# working.net
KiCad netlist of a schematic drawn in EAGLE
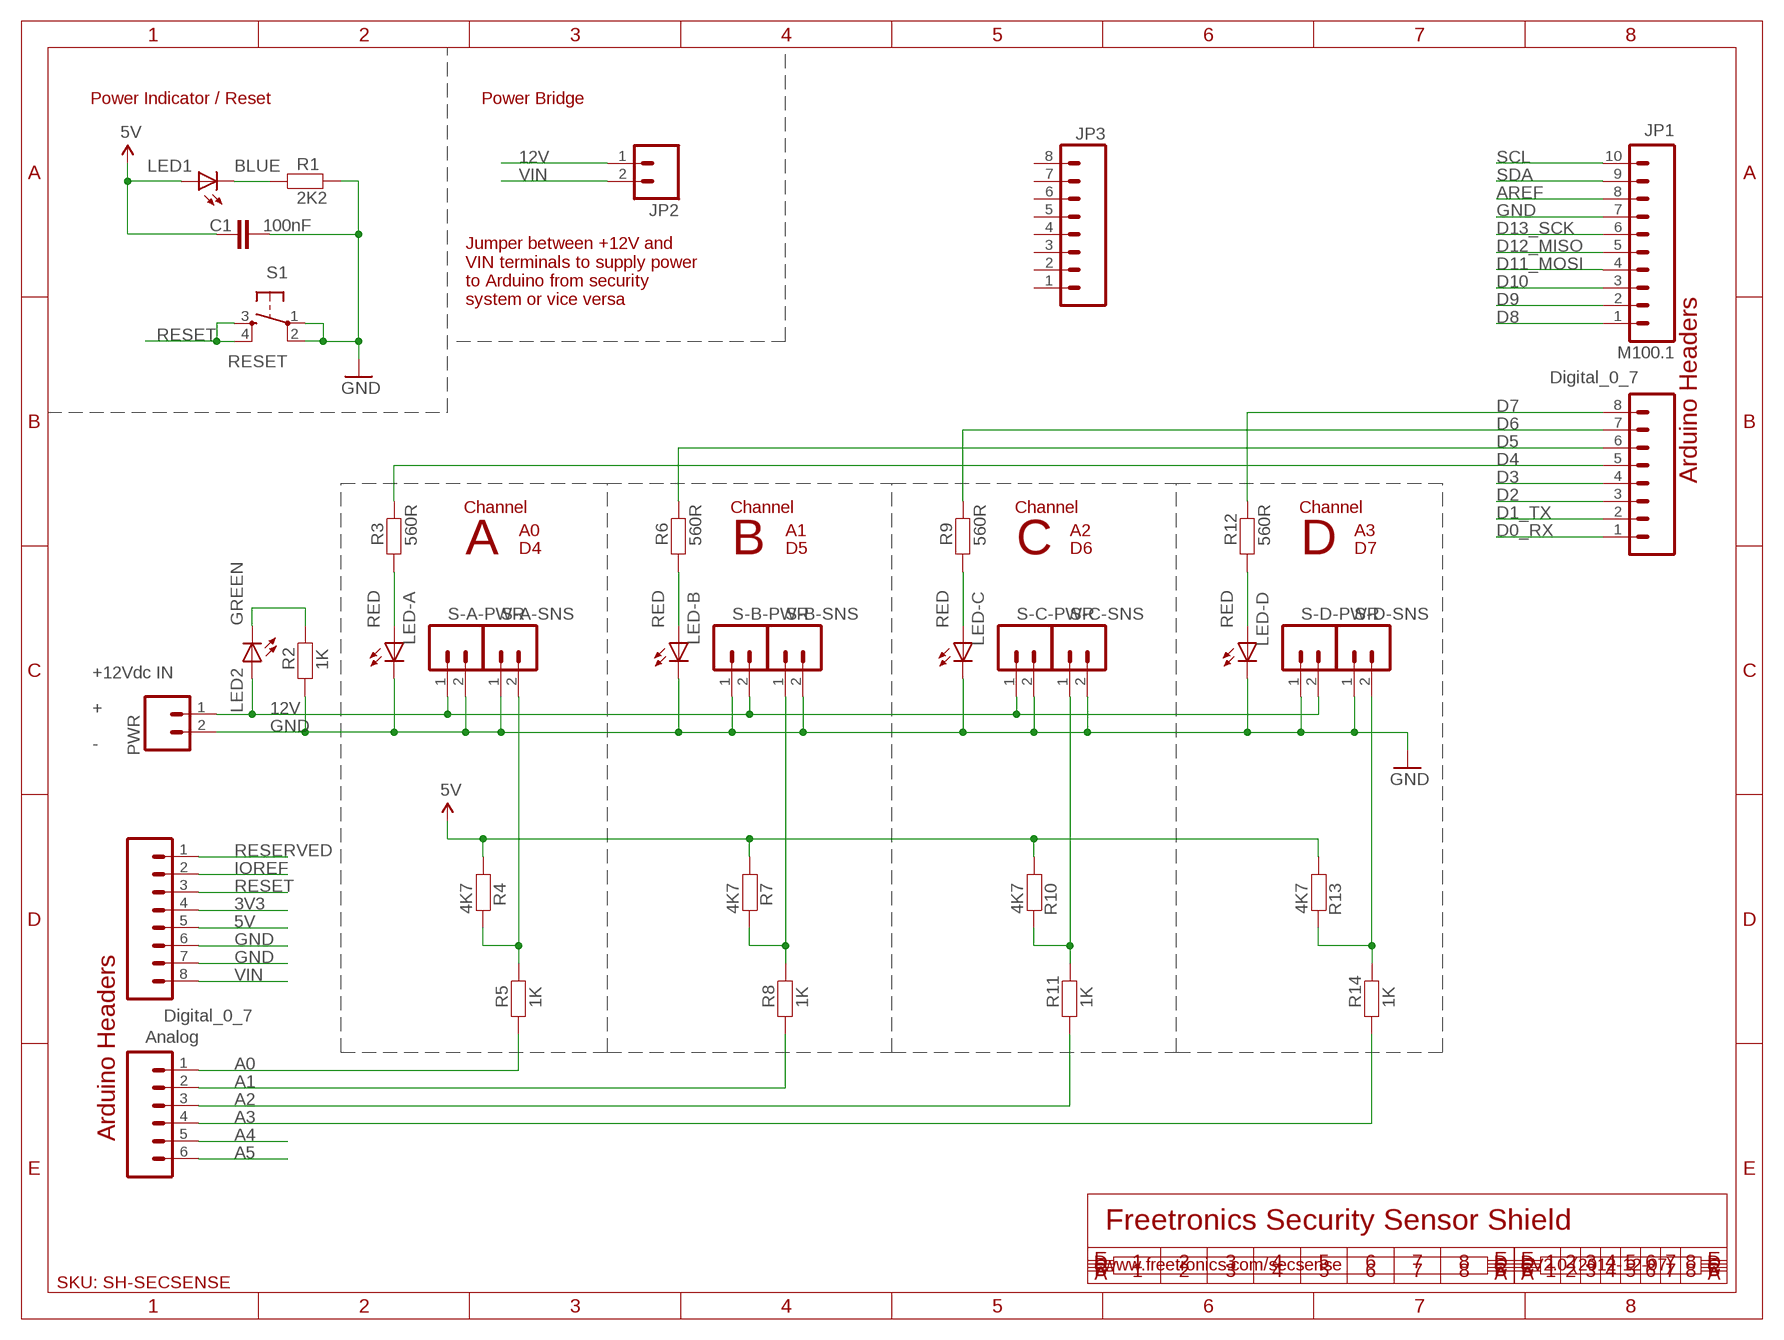
[diagram p0: schematic, sheet 1]

(export (version "E")
  (design (tool "Eeschema 10.0.6"))
  (components
    (comp (ref "C1")
      (value "100nF")
      (footprint "eagle-import:FREETRONICS_CAP-PTH-SMALL")
      (libsource (lib "eagle-import") (part "FREETRONICS_CAPPTH"))
    )
    (comp (ref "J1")
      (value "Digital_0_7")
      (footprint "eagle-import:1X08")
      (libsource (lib "eagle-import") (part "M08"))
    )
    (comp (ref "J2")
      (value "Analog")
      (footprint "eagle-import:1X06")
      (libsource (lib "eagle-import") (part "M06SIP"))
    )
    (comp (ref "J3")
      (value "Digital_0_7")
      (footprint "eagle-import:1X08")
      (libsource (lib "eagle-import") (part "M08"))
    )
    (comp (ref "JP1")
      (value "M100.1")
      (footprint "eagle-import:1X10")
      (libsource (lib "eagle-import") (part "M100.1"))
    )
    (comp (ref "JP2")
      (value "M02PTH")
      (footprint "eagle-import:1X02")
      (libsource (lib "eagle-import") (part "freetronics-original_M02PTH"))
    )
    (comp (ref "JP3")
      (value "M08")
      (footprint "eagle-import:TERMINALBLOCK_3.5MM_8")
      (libsource (lib "eagle-import") (part "freetronics-master-v1_M08"))
    )
    (comp (ref "LED-A")
      (value "RED")
      (footprint "eagle-import:LED3MM")
      (libsource (lib "eagle-import") (part "LED3MM"))
    )
    (comp (ref "LED-B")
      (value "RED")
      (footprint "eagle-import:LED3MM")
      (libsource (lib "eagle-import") (part "LED3MM"))
    )
    (comp (ref "LED-C")
      (value "RED")
      (footprint "eagle-import:LED3MM")
      (libsource (lib "eagle-import") (part "LED3MM"))
    )
    (comp (ref "LED-D")
      (value "RED")
      (footprint "eagle-import:LED3MM")
      (libsource (lib "eagle-import") (part "LED3MM"))
    )
    (comp (ref "LED1")
      (value "BLUE")
      (footprint "eagle-import:LED3MM")
      (libsource (lib "eagle-import") (part "LED3MM"))
    )
    (comp (ref "LED2")
      (value "GREEN")
      (footprint "eagle-import:LED3MM")
      (libsource (lib "eagle-import") (part "LED3MM"))
    )
    (comp (ref "PWR")
      (value "M025MM")
      (footprint "eagle-import:SCREWTERMINAL-5MM-2")
      (libsource (lib "eagle-import") (part "M025MM"))
    )
    (comp (ref "R1")
      (value "2K2")
      (footprint "eagle-import:FREETRONICS_AXIAL-0.4")
      (libsource (lib "eagle-import") (part "FREETRONICS_RESISTORPTH2"))
    )
    (comp (ref "R2")
      (value "1K")
      (footprint "eagle-import:FREETRONICS_AXIAL-0.4")
      (libsource (lib "eagle-import") (part "FREETRONICS_RESISTORPTH2"))
    )
    (comp (ref "R3")
      (value "560R")
      (footprint "eagle-import:FREETRONICS_AXIAL-0.4")
      (libsource (lib "eagle-import") (part "FREETRONICS_RESISTORPTH2"))
    )
    (comp (ref "R4")
      (value "4K7")
      (footprint "eagle-import:FREETRONICS_AXIAL-0.4")
      (libsource (lib "eagle-import") (part "FREETRONICS_RESISTORPTH2"))
    )
    (comp (ref "R5")
      (value "1K")
      (footprint "eagle-import:FREETRONICS_AXIAL-0.4")
      (libsource (lib "eagle-import") (part "FREETRONICS_RESISTORPTH2"))
    )
    (comp (ref "R6")
      (value "560R")
      (footprint "eagle-import:FREETRONICS_AXIAL-0.4")
      (libsource (lib "eagle-import") (part "FREETRONICS_RESISTORPTH2"))
    )
    (comp (ref "R7")
      (value "4K7")
      (footprint "eagle-import:FREETRONICS_AXIAL-0.4")
      (libsource (lib "eagle-import") (part "FREETRONICS_RESISTORPTH2"))
    )
    (comp (ref "R8")
      (value "1K")
      (footprint "eagle-import:FREETRONICS_AXIAL-0.4")
      (libsource (lib "eagle-import") (part "FREETRONICS_RESISTORPTH2"))
    )
    (comp (ref "R9")
      (value "560R")
      (footprint "eagle-import:FREETRONICS_AXIAL-0.4")
      (libsource (lib "eagle-import") (part "FREETRONICS_RESISTORPTH2"))
    )
    (comp (ref "R10")
      (value "4K7")
      (footprint "eagle-import:FREETRONICS_AXIAL-0.4")
      (libsource (lib "eagle-import") (part "FREETRONICS_RESISTORPTH2"))
    )
    (comp (ref "R11")
      (value "1K")
      (footprint "eagle-import:FREETRONICS_AXIAL-0.4")
      (libsource (lib "eagle-import") (part "FREETRONICS_RESISTORPTH2"))
    )
    (comp (ref "R12")
      (value "560R")
      (footprint "eagle-import:FREETRONICS_AXIAL-0.4")
      (libsource (lib "eagle-import") (part "FREETRONICS_RESISTORPTH2"))
    )
    (comp (ref "R13")
      (value "4K7")
      (footprint "eagle-import:FREETRONICS_AXIAL-0.4")
      (libsource (lib "eagle-import") (part "FREETRONICS_RESISTORPTH2"))
    )
    (comp (ref "R14")
      (value "1K")
      (footprint "eagle-import:FREETRONICS_AXIAL-0.4")
      (libsource (lib "eagle-import") (part "FREETRONICS_RESISTORPTH2"))
    )
    (comp (ref "S-A-PWR")
      (value "M025MM")
      (footprint "eagle-import:SCREWTERMINAL-5MM-2")
      (libsource (lib "eagle-import") (part "M025MM"))
    )
    (comp (ref "S-A-SNS")
      (value "M025MM")
      (footprint "eagle-import:SCREWTERMINAL-5MM-2")
      (libsource (lib "eagle-import") (part "M025MM"))
    )
    (comp (ref "S-B-PWR")
      (value "M025MM")
      (footprint "eagle-import:SCREWTERMINAL-5MM-2")
      (libsource (lib "eagle-import") (part "M025MM"))
    )
    (comp (ref "S-B-SNS")
      (value "M025MM")
      (footprint "eagle-import:SCREWTERMINAL-5MM-2")
      (libsource (lib "eagle-import") (part "M025MM"))
    )
    (comp (ref "S-C-PWR")
      (value "M025MM")
      (footprint "eagle-import:SCREWTERMINAL-5MM-2")
      (libsource (lib "eagle-import") (part "M025MM"))
    )
    (comp (ref "S-C-SNS")
      (value "M025MM")
      (footprint "eagle-import:SCREWTERMINAL-5MM-2")
      (libsource (lib "eagle-import") (part "M025MM"))
    )
    (comp (ref "S-D-PWR")
      (value "M025MM")
      (footprint "eagle-import:SCREWTERMINAL-5MM-2")
      (libsource (lib "eagle-import") (part "M025MM"))
    )
    (comp (ref "S-D-SNS")
      (value "M025MM")
      (footprint "eagle-import:SCREWTERMINAL-5MM-2")
      (libsource (lib "eagle-import") (part "M025MM"))
    )
    (comp (ref "S1")
      (value "RESET")
      (footprint "eagle-import:FREETRONICS_TACTILE-PTH")
      (libsource (lib "eagle-import") (part "FREETRONICS_TAC_SWITCHPTH"))
    )
  )
  (nets
    (net (code "1") (name "/3V3") (class "Default")
      (node (ref "J3") (pin "4") (pinfunction "4_4") (pintype "passive"))
    )
    (net (code "2") (name "/12V") (class "Default")
      (node (ref "JP2") (pin "1") (pinfunction "1_1") (pintype "passive"))
      (node (ref "LED2") (pin "A") (pinfunction "A_A") (pintype "passive"))
      (node (ref "PWR") (pin "1") (pinfunction "1_1") (pintype "passive"))
      (node (ref "S-A-PWR") (pin "1") (pinfunction "1_1") (pintype "passive"))
      (node (ref "S-B-PWR") (pin "2") (pinfunction "2_2") (pintype "passive"))
      (node (ref "S-C-PWR") (pin "1") (pinfunction "1_1") (pintype "passive"))
      (node (ref "S-D-PWR") (pin "2") (pinfunction "2_2") (pintype "passive"))
    )
    (net (code "3") (name "/A0") (class "Default")
      (node (ref "J2") (pin "1") (pinfunction "1_1") (pintype "passive"))
      (node (ref "R5") (pin "P$1") (pinfunction "1_P$1") (pintype "passive"))
    )
    (net (code "4") (name "/A1") (class "Default")
      (node (ref "J2") (pin "2") (pinfunction "2_2") (pintype "passive"))
      (node (ref "R8") (pin "P$1") (pinfunction "1_P$1") (pintype "passive"))
    )
    (net (code "5") (name "/A2") (class "Default")
      (node (ref "J2") (pin "3") (pinfunction "3_3") (pintype "passive"))
      (node (ref "R11") (pin "P$1") (pinfunction "1_P$1") (pintype "passive"))
    )
    (net (code "6") (name "/A3") (class "Default")
      (node (ref "J2") (pin "4") (pinfunction "4_4") (pintype "passive"))
      (node (ref "R14") (pin "P$1") (pinfunction "1_P$1") (pintype "passive"))
    )
    (net (code "7") (name "/A4") (class "Default")
      (node (ref "J2") (pin "5") (pinfunction "5_5") (pintype "passive"))
    )
    (net (code "8") (name "/A5") (class "Default")
      (node (ref "J2") (pin "6") (pinfunction "6_6") (pintype "passive"))
    )
    (net (code "9") (name "/AREF") (class "Default")
      (node (ref "JP1") (pin "8") (pinfunction "8_8") (pintype "passive"))
    )
    (net (code "10") (name "/D0_RX") (class "Default")
      (node (ref "J1") (pin "1") (pinfunction "1_1") (pintype "passive"))
    )
    (net (code "11") (name "/D1_TX") (class "Default")
      (node (ref "J1") (pin "2") (pinfunction "2_2") (pintype "passive"))
    )
    (net (code "12") (name "/D2") (class "Default")
      (node (ref "J1") (pin "3") (pinfunction "3_3") (pintype "passive"))
    )
    (net (code "13") (name "/D3") (class "Default")
      (node (ref "J1") (pin "4") (pinfunction "4_4") (pintype "passive"))
    )
    (net (code "14") (name "/D4") (class "Default")
      (node (ref "J1") (pin "5") (pinfunction "5_5") (pintype "passive"))
      (node (ref "R3") (pin "P$2") (pinfunction "2_P$2") (pintype "passive"))
    )
    (net (code "15") (name "/D5") (class "Default")
      (node (ref "J1") (pin "6") (pinfunction "6_6") (pintype "passive"))
      (node (ref "R6") (pin "P$2") (pinfunction "2_P$2") (pintype "passive"))
    )
    (net (code "16") (name "/D6") (class "Default")
      (node (ref "J1") (pin "7") (pinfunction "7_7") (pintype "passive"))
      (node (ref "R9") (pin "P$2") (pinfunction "2_P$2") (pintype "passive"))
    )
    (net (code "17") (name "/D7") (class "Default")
      (node (ref "J1") (pin "8") (pinfunction "8_8") (pintype "passive"))
      (node (ref "R12") (pin "P$2") (pinfunction "2_P$2") (pintype "passive"))
    )
    (net (code "18") (name "/D8") (class "Default")
      (node (ref "JP1") (pin "1") (pinfunction "1_1") (pintype "passive"))
    )
    (net (code "19") (name "/D9") (class "Default")
      (node (ref "JP1") (pin "2") (pinfunction "2_2") (pintype "passive"))
    )
    (net (code "20") (name "/D10") (class "Default")
      (node (ref "JP1") (pin "3") (pinfunction "3_3") (pintype "passive"))
    )
    (net (code "21") (name "/D11_MOSI") (class "Default")
      (node (ref "JP1") (pin "4") (pinfunction "4_4") (pintype "passive"))
    )
    (net (code "22") (name "/D12_MISO") (class "Default")
      (node (ref "JP1") (pin "5") (pinfunction "5_5") (pintype "passive"))
    )
    (net (code "23") (name "/D13_SCK") (class "Default")
      (node (ref "JP1") (pin "6") (pinfunction "6_6") (pintype "passive"))
    )
    (net (code "24") (name "/IOREF") (class "Default")
      (node (ref "J3") (pin "2") (pinfunction "2_2") (pintype "passive"))
    )
    (net (code "25") (name "/RESERVED") (class "Default")
      (node (ref "J3") (pin "1") (pinfunction "1_1") (pintype "passive"))
    )
    (net (code "26") (name "/RESET") (class "Default")
      (node (ref "J3") (pin "3") (pinfunction "3_3") (pintype "passive"))
      (node (ref "S1") (pin "3") (pinfunction "3_3") (pintype "passive"))
      (node (ref "S1") (pin "4") (pinfunction "4_4") (pintype "passive"))
    )
    (net (code "27") (name "/SCL") (class "Default")
      (node (ref "JP1") (pin "10") (pinfunction "10_10") (pintype "passive"))
    )
    (net (code "28") (name "/SDA") (class "Default")
      (node (ref "JP1") (pin "9") (pinfunction "9_9") (pintype "passive"))
    )
    (net (code "29") (name "/VIN") (class "Default")
      (node (ref "J3") (pin "8") (pinfunction "8_8") (pintype "passive"))
      (node (ref "JP2") (pin "2") (pinfunction "2_2") (pintype "passive"))
    )
    (net (code "30") (name "5V") (class "Default")
      (node (ref "C1") (pin "1") (pinfunction "1_1") (pintype "passive"))
      (node (ref "J3") (pin "5") (pinfunction "5_5") (pintype "passive"))
      (node (ref "LED1") (pin "A") (pinfunction "A_A") (pintype "passive"))
      (node (ref "R10") (pin "P$1") (pinfunction "1_P$1") (pintype "passive"))
      (node (ref "R13") (pin "P$1") (pinfunction "1_P$1") (pintype "passive"))
      (node (ref "R4") (pin "P$1") (pinfunction "1_P$1") (pintype "passive"))
      (node (ref "R7") (pin "P$1") (pinfunction "1_P$1") (pintype "passive"))
    )
    (net (code "31") (name "GND") (class "Default")
      (node (ref "C1") (pin "2") (pinfunction "2_2") (pintype "passive"))
      (node (ref "J3") (pin "6") (pinfunction "6_6") (pintype "passive"))
      (node (ref "J3") (pin "7") (pinfunction "7_7") (pintype "passive"))
      (node (ref "JP1") (pin "7") (pinfunction "7_7") (pintype "passive"))
      (node (ref "LED-A") (pin "K") (pinfunction "C_K") (pintype "passive"))
      (node (ref "LED-B") (pin "K") (pinfunction "C_K") (pintype "passive"))
      (node (ref "LED-C") (pin "K") (pinfunction "C_K") (pintype "passive"))
      (node (ref "LED-D") (pin "K") (pinfunction "C_K") (pintype "passive"))
      (node (ref "PWR") (pin "2") (pinfunction "2_2") (pintype "passive"))
      (node (ref "R1") (pin "P$2") (pinfunction "2_P$2") (pintype "passive"))
      (node (ref "R2") (pin "P$1") (pinfunction "1_P$1") (pintype "passive"))
      (node (ref "S-A-PWR") (pin "2") (pinfunction "2_2") (pintype "passive"))
      (node (ref "S-A-SNS") (pin "1") (pinfunction "1_1") (pintype "passive"))
      (node (ref "S-B-PWR") (pin "1") (pinfunction "1_1") (pintype "passive"))
      (node (ref "S-B-SNS") (pin "2") (pinfunction "2_2") (pintype "passive"))
      (node (ref "S-C-PWR") (pin "2") (pinfunction "2_2") (pintype "passive"))
      (node (ref "S-C-SNS") (pin "2") (pinfunction "2_2") (pintype "passive"))
      (node (ref "S-D-PWR") (pin "1") (pinfunction "1_1") (pintype "passive"))
      (node (ref "S-D-SNS") (pin "1") (pinfunction "1_1") (pintype "passive"))
      (node (ref "S1") (pin "1") (pinfunction "1_1") (pintype "passive"))
      (node (ref "S1") (pin "2") (pinfunction "2_2") (pintype "passive"))
    )
    (net (code "32") (name "Net-(LED1-C)") (class "Default")
      (node (ref "LED1") (pin "K") (pinfunction "C_K") (pintype "passive"))
      (node (ref "R1") (pin "P$1") (pinfunction "1_P$1") (pintype "passive"))
    )
    (net (code "33") (name "Net-(LED2-C)") (class "Default")
      (node (ref "LED2") (pin "K") (pinfunction "C_K") (pintype "passive"))
      (node (ref "R2") (pin "P$2") (pinfunction "2_P$2") (pintype "passive"))
    )
    (net (code "34") (name "Net-(R3-1)") (class "Default")
      (node (ref "LED-A") (pin "A") (pinfunction "A_A") (pintype "passive"))
      (node (ref "R3") (pin "P$1") (pinfunction "1_P$1") (pintype "passive"))
    )
    (net (code "35") (name "Net-(R4-2)") (class "Default")
      (node (ref "R4") (pin "P$2") (pinfunction "2_P$2") (pintype "passive"))
      (node (ref "R5") (pin "P$2") (pinfunction "2_P$2") (pintype "passive"))
      (node (ref "S-A-SNS") (pin "2") (pinfunction "2_2") (pintype "passive"))
    )
    (net (code "36") (name "Net-(R6-1)") (class "Default")
      (node (ref "LED-B") (pin "A") (pinfunction "A_A") (pintype "passive"))
      (node (ref "R6") (pin "P$1") (pinfunction "1_P$1") (pintype "passive"))
    )
    (net (code "37") (name "Net-(R7-2)") (class "Default")
      (node (ref "R7") (pin "P$2") (pinfunction "2_P$2") (pintype "passive"))
      (node (ref "R8") (pin "P$2") (pinfunction "2_P$2") (pintype "passive"))
      (node (ref "S-B-SNS") (pin "1") (pinfunction "1_1") (pintype "passive"))
    )
    (net (code "38") (name "Net-(R9-1)") (class "Default")
      (node (ref "LED-C") (pin "A") (pinfunction "A_A") (pintype "passive"))
      (node (ref "R9") (pin "P$1") (pinfunction "1_P$1") (pintype "passive"))
    )
    (net (code "39") (name "Net-(R10-2)") (class "Default")
      (node (ref "R10") (pin "P$2") (pinfunction "2_P$2") (pintype "passive"))
      (node (ref "R11") (pin "P$2") (pinfunction "2_P$2") (pintype "passive"))
      (node (ref "S-C-SNS") (pin "1") (pinfunction "1_1") (pintype "passive"))
    )
    (net (code "40") (name "Net-(R12-1)") (class "Default")
      (node (ref "LED-D") (pin "A") (pinfunction "A_A") (pintype "passive"))
      (node (ref "R12") (pin "P$1") (pinfunction "1_P$1") (pintype "passive"))
    )
    (net (code "41") (name "Net-(R13-2)") (class "Default")
      (node (ref "R13") (pin "P$2") (pinfunction "2_P$2") (pintype "passive"))
      (node (ref "R14") (pin "P$2") (pinfunction "2_P$2") (pintype "passive"))
      (node (ref "S-D-SNS") (pin "2") (pinfunction "2_2") (pintype "passive"))
    )
    (net (code "42") (name "unconnected-(JP3-Pad1)") (class "Default")
      (node (ref "JP3") (pin "1") (pinfunction "1_1") (pintype "passive"))
    )
    (net (code "43") (name "unconnected-(JP3-Pad2)") (class "Default")
      (node (ref "JP3") (pin "2") (pinfunction "2_2") (pintype "passive"))
    )
    (net (code "44") (name "unconnected-(JP3-Pad3)") (class "Default")
      (node (ref "JP3") (pin "3") (pinfunction "3_3") (pintype "passive"))
    )
    (net (code "45") (name "unconnected-(JP3-Pad4)") (class "Default")
      (node (ref "JP3") (pin "4") (pinfunction "4_4") (pintype "passive"))
    )
    (net (code "46") (name "unconnected-(JP3-Pad5)") (class "Default")
      (node (ref "JP3") (pin "5") (pinfunction "5_5") (pintype "passive"))
    )
    (net (code "47") (name "unconnected-(JP3-Pad6)") (class "Default")
      (node (ref "JP3") (pin "6") (pinfunction "6_6") (pintype "passive"))
    )
    (net (code "48") (name "unconnected-(JP3-Pad7)") (class "Default")
      (node (ref "JP3") (pin "7") (pinfunction "7_7") (pintype "passive"))
    )
    (net (code "49") (name "unconnected-(JP3-Pad8)") (class "Default")
      (node (ref "JP3") (pin "8") (pinfunction "8_8") (pintype "passive"))
    )
  )
)
